# Pulse_Ox_PCB_board.net
KiCad netlist of a schematic drawn in EAGLE
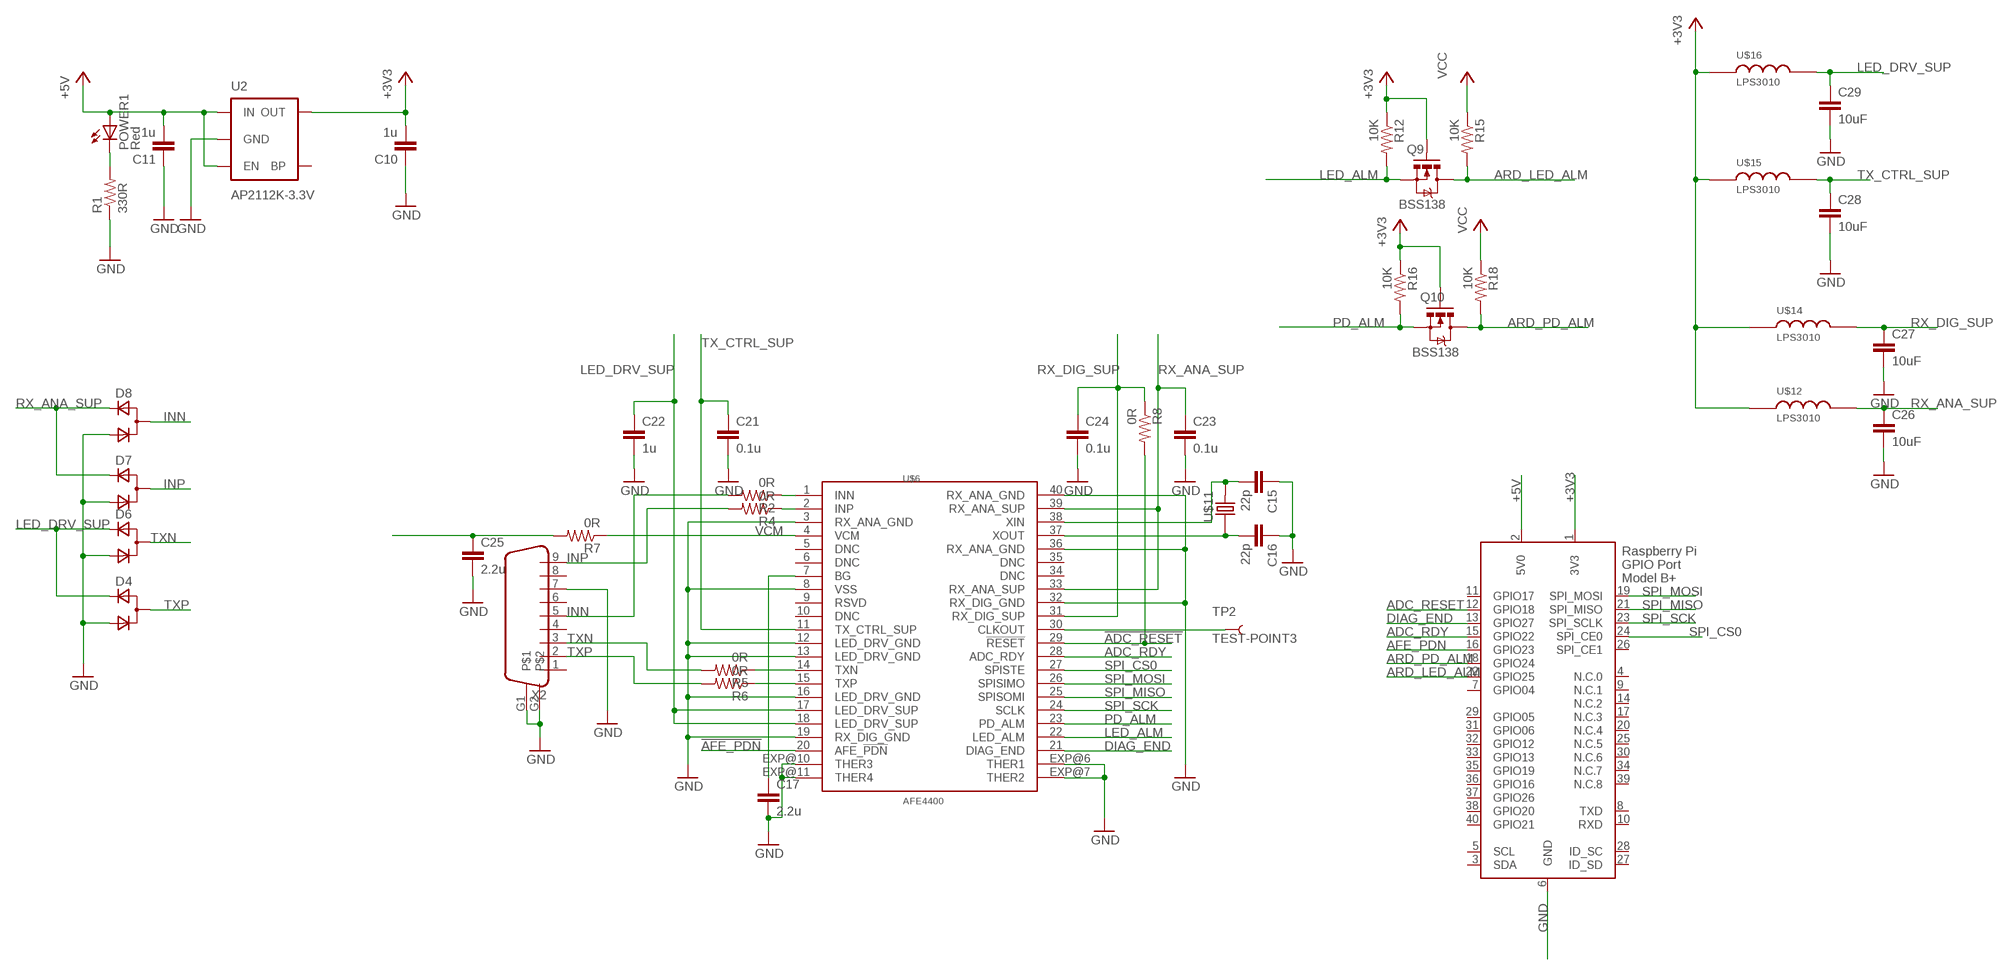
[diagram p0: schematic, sheet 1]

(export (version "E")
  (design (tool "Eeschema 10.0.6"))
  (components
    (comp (ref "C10")
      (value "1u")
      (footprint "eagle-import:C0805")
      (libsource (lib "eagle-import") (part "C-EUC0805"))
    )
    (comp (ref "C11")
      (value "1u")
      (footprint "eagle-import:C0805")
      (libsource (lib "eagle-import") (part "C-EUC0805"))
    )
    (comp (ref "C15")
      (value "22p")
      (footprint "eagle-import:C0402")
      (libsource (lib "eagle-import") (part "C-EUC0402"))
    )
    (comp (ref "C16")
      (value "22p")
      (footprint "eagle-import:C0402")
      (libsource (lib "eagle-import") (part "C-EUC0402"))
    )
    (comp (ref "C17")
      (value "2.2u")
      (footprint "eagle-import:C0402")
      (libsource (lib "eagle-import") (part "C-EUC0402"))
    )
    (comp (ref "C21")
      (value "0.1u")
      (footprint "eagle-import:C0805")
      (libsource (lib "eagle-import") (part "C-EUC0805"))
    )
    (comp (ref "C22")
      (value "1u")
      (footprint "eagle-import:C0805")
      (libsource (lib "eagle-import") (part "C-EUC0805"))
    )
    (comp (ref "C23")
      (value "0.1u")
      (footprint "eagle-import:C0805")
      (libsource (lib "eagle-import") (part "C-EUC0805"))
    )
    (comp (ref "C24")
      (value "0.1u")
      (footprint "eagle-import:C0805")
      (libsource (lib "eagle-import") (part "C-EUC0805"))
    )
    (comp (ref "C25")
      (value "2.2u")
      (footprint "eagle-import:C0402")
      (libsource (lib "eagle-import") (part "C-EUC0402"))
    )
    (comp (ref "C26")
      (value "10uF")
      (footprint "eagle-import:C0805")
      (libsource (lib "eagle-import") (part "C-EUC0805"))
    )
    (comp (ref "C27")
      (value "10uF")
      (footprint "eagle-import:C0805")
      (libsource (lib "eagle-import") (part "C-EUC0805"))
    )
    (comp (ref "C28")
      (value "10uF")
      (footprint "eagle-import:C0805")
      (libsource (lib "eagle-import") (part "C-EUC0805"))
    )
    (comp (ref "C29")
      (value "10uF")
      (footprint "eagle-import:C0805")
      (libsource (lib "eagle-import") (part "C-EUC0805"))
    )
    (comp (ref "D4")
      (value "D_ACACSOT323")
      (footprint "eagle-import:SOT323")
      (libsource (lib "eagle-import") (part "D_ACACSOT323"))
    )
    (comp (ref "D6")
      (value "D_ACACSOT323")
      (footprint "eagle-import:SOT323")
      (libsource (lib "eagle-import") (part "D_ACACSOT323"))
    )
    (comp (ref "D7")
      (value "D_ACACSOT323")
      (footprint "eagle-import:SOT323")
      (libsource (lib "eagle-import") (part "D_ACACSOT323"))
    )
    (comp (ref "D8")
      (value "D_ACACSOT323")
      (footprint "eagle-import:SOT323")
      (libsource (lib "eagle-import") (part "D_ACACSOT323"))
    )
    (comp (ref "POWER1")
      (value "Red")
      (footprint "eagle-import:CHIPLED_0603")
      (libsource (lib "eagle-import") (part "LEDCHIPLED_0603"))
    )
    (comp (ref "Q9")
      (value "BSS138")
      (footprint "eagle-import:SOT23-3")
      (libsource (lib "eagle-import") (part "MOSFET-NCHANNELSMD"))
    )
    (comp (ref "Q10")
      (value "BSS138")
      (footprint "eagle-import:SOT23-3")
      (libsource (lib "eagle-import") (part "MOSFET-NCHANNELSMD"))
    )
    (comp (ref "R1")
      (value "330R")
      (footprint "eagle-import:R0805")
      (libsource (lib "eagle-import") (part "R-US_R0805"))
    )
    (comp (ref "R2")
      (value "0R")
      (footprint "eagle-import:R0402")
      (libsource (lib "eagle-import") (part "R-US_R0402"))
    )
    (comp (ref "R4")
      (value "0R")
      (footprint "eagle-import:R0402")
      (libsource (lib "eagle-import") (part "R-US_R0402"))
    )
    (comp (ref "R5")
      (value "0R")
      (footprint "eagle-import:R0805")
      (libsource (lib "eagle-import") (part "R-US_R0805"))
    )
    (comp (ref "R6")
      (value "0R")
      (footprint "eagle-import:R0805")
      (libsource (lib "eagle-import") (part "R-US_R0805"))
    )
    (comp (ref "R7")
      (value "0R")
      (footprint "eagle-import:R0402")
      (libsource (lib "eagle-import") (part "R-US_R0402"))
    )
    (comp (ref "R8")
      (value "0R")
      (footprint "eagle-import:R0805")
      (libsource (lib "eagle-import") (part "R-US_R0805"))
    )
    (comp (ref "R12")
      (value "10K")
      (footprint "eagle-import:0805")
      (libsource (lib "eagle-import") (part "RESISTOR0805-RES"))
    )
    (comp (ref "R15")
      (value "10K")
      (footprint "eagle-import:0805")
      (libsource (lib "eagle-import") (part "RESISTOR0805-RES"))
    )
    (comp (ref "R16")
      (value "10K")
      (footprint "eagle-import:0805")
      (libsource (lib "eagle-import") (part "RESISTOR0805-RES"))
    )
    (comp (ref "R18")
      (value "10K")
      (footprint "eagle-import:0805")
      (libsource (lib "eagle-import") (part "RESISTOR0805-RES"))
    )
    (comp (ref "TP2")
      (value "TEST-POINT3")
      (footprint "eagle-import:PAD.03X.03")
      (libsource (lib "eagle-import") (part "TEST-POINT3"))
    )
    (comp (ref "U$6")
      (value "AFE4400")
      (footprint "eagle-import:QFN-40")
      (libsource (lib "eagle-import") (part "AFE4400"))
    )
    (comp (ref "U$11")
      (value "ABM3")
      (footprint "eagle-import:ABM3")
      (libsource (lib "eagle-import") (part "ABM3"))
    )
    (comp (ref "U$12")
      (value "LPS3010")
      (footprint "eagle-import:LPS")
      (libsource (lib "eagle-import") (part "LPS"))
    )
    (comp (ref "U$14")
      (value "LPS3010")
      (footprint "eagle-import:LPS")
      (libsource (lib "eagle-import") (part "LPS"))
    )
    (comp (ref "U$15")
      (value "LPS3010")
      (footprint "eagle-import:LPS")
      (libsource (lib "eagle-import") (part "LPS"))
    )
    (comp (ref "U$16")
      (value "LPS3010")
      (footprint "eagle-import:LPS")
      (libsource (lib "eagle-import") (part "LPS"))
    )
    (comp (ref "U2")
      (value "AP2112K-3.3V")
      (footprint "eagle-import:SOT23-5")
      (libsource (lib "eagle-import") (part "V_REG_LDOSMD"))
    )
    (comp (ref "X2")
      (value "DB9")
      (footprint "eagle-import:DB9")
      (libsource (lib "eagle-import") (part "DB9"))
    )
    (comp (ref "X3")
      (value "RASPI_BOARD_B+_HD")
      (footprint "eagle-import:RASPI_BOARD_B+HAT_DF")
      (libsource (lib "eagle-import") (part "RASPI_BOARD_B+_HD"))
    )
  )
  (nets
    (net (code "1") (name "+3V3") (class "Default")
      (node (ref "C10") (pin "2") (pinfunction "2_2") (pintype "passive"))
      (node (ref "Q10") (pin "1") (pinfunction "G_1") (pintype "passive"))
      (node (ref "Q9") (pin "1") (pinfunction "G_1") (pintype "passive"))
      (node (ref "R12") (pin "1") (pinfunction "1_1") (pintype "passive"))
      (node (ref "R16") (pin "1") (pinfunction "1_1") (pintype "passive"))
      (node (ref "U$12") (pin "1") (pinfunction "P$1_1") (pintype "bidirectional"))
      (node (ref "U$14") (pin "1") (pinfunction "P$1_1") (pintype "bidirectional"))
      (node (ref "U$15") (pin "1") (pinfunction "P$1_1") (pintype "bidirectional"))
      (node (ref "U$16") (pin "1") (pinfunction "P$1_1") (pintype "bidirectional"))
      (node (ref "U2") (pin "5") (pinfunction "OUT_5") (pintype "passive"))
      (node (ref "X3") (pin "1") (pinfunction "3V3_1") (pintype "power_in"))
    )
    (net (code "2") (name "+5V") (class "Default")
      (node (ref "C11") (pin "2") (pinfunction "2_2") (pintype "passive"))
      (node (ref "POWER1") (pin "A") (pinfunction "A_A") (pintype "passive"))
      (node (ref "U2") (pin "1") (pinfunction "IN_1") (pintype "input"))
      (node (ref "U2") (pin "3") (pinfunction "EN_3") (pintype "input"))
      (node (ref "X3") (pin "2") (pinfunction "5V0_2") (pintype "power_in"))
    )
    (net (code "3") (name "/ADC_RDY") (class "Default")
      (node (ref "U$6") (pin "28") (pinfunction "ADC_RDY_28") (pintype "bidirectional"))
      (node (ref "X3") (pin "15") (pinfunction "GPIO22_15") (pintype "bidirectional"))
    )
    (net (code "4") (name "/ADC_RESET") (class "Default")
      (node (ref "X3") (pin "12") (pinfunction "GPIO18_12") (pintype "bidirectional"))
    )
    (net (code "5") (name "/AFE_PDN") (class "Default")
      (node (ref "X3") (pin "16") (pinfunction "GPIO23_16") (pintype "bidirectional"))
    )
    (net (code "6") (name "/ARD_LED_ALM") (class "Default")
      (node (ref "Q9") (pin "3") (pinfunction "D_3") (pintype "passive"))
      (node (ref "R15") (pin "2") (pinfunction "2_2") (pintype "passive"))
      (node (ref "X3") (pin "22") (pinfunction "GPIO25_22") (pintype "bidirectional"))
    )
    (net (code "7") (name "/ARD_PD_ALM") (class "Default")
      (node (ref "Q10") (pin "3") (pinfunction "D_3") (pintype "passive"))
      (node (ref "R18") (pin "2") (pinfunction "2_2") (pintype "passive"))
      (node (ref "X3") (pin "18") (pinfunction "GPIO24_18") (pintype "bidirectional"))
    )
    (net (code "8") (name "/DIAG_END") (class "Default")
      (node (ref "U$6") (pin "21") (pinfunction "DIAG_END_21") (pintype "bidirectional"))
      (node (ref "X3") (pin "13") (pinfunction "GPIO27_13") (pintype "bidirectional"))
    )
    (net (code "9") (name "/INN") (class "Default")
      (node (ref "D8") (pin "1") (pinfunction "CA_1") (pintype "passive"))
      (node (ref "R2") (pin "2") (pinfunction "2_2") (pintype "passive"))
      (node (ref "X2") (pin "5") (pinfunction "5_5") (pintype "passive"))
    )
    (net (code "10") (name "/INP") (class "Default")
      (node (ref "D7") (pin "1") (pinfunction "CA_1") (pintype "passive"))
      (node (ref "R4") (pin "2") (pinfunction "2_2") (pintype "passive"))
      (node (ref "X2") (pin "9") (pinfunction "9_9") (pintype "passive"))
    )
    (net (code "11") (name "/LED_ALM") (class "Default")
      (node (ref "Q9") (pin "2") (pinfunction "S_2") (pintype "passive"))
      (node (ref "R12") (pin "2") (pinfunction "2_2") (pintype "passive"))
      (node (ref "U$6") (pin "22") (pinfunction "LED_ALM_22") (pintype "bidirectional"))
    )
    (net (code "12") (name "/LED_DRV_SUP") (class "Default")
      (node (ref "C22") (pin "1") (pinfunction "1_1") (pintype "passive"))
      (node (ref "C29") (pin "1") (pinfunction "1_1") (pintype "passive"))
      (node (ref "D4") (pin "3") (pinfunction "A_3") (pintype "passive"))
      (node (ref "D6") (pin "3") (pinfunction "A_3") (pintype "passive"))
      (node (ref "U$16") (pin "2") (pinfunction "P$2_2") (pintype "bidirectional"))
      (node (ref "U$6") (pin "17") (pinfunction "LED_DRV_SUP_17") (pintype "bidirectional"))
      (node (ref "U$6") (pin "18") (pinfunction "LED_DRV_SUP_18") (pintype "bidirectional"))
    )
    (net (code "13") (name "/PD_ALM") (class "Default")
      (node (ref "Q10") (pin "2") (pinfunction "S_2") (pintype "passive"))
      (node (ref "R16") (pin "2") (pinfunction "2_2") (pintype "passive"))
      (node (ref "U$6") (pin "23") (pinfunction "PD_ALM_23") (pintype "bidirectional"))
    )
    (net (code "14") (name "/RX_ANA_SUP") (class "Default")
      (node (ref "C23") (pin "1") (pinfunction "1_1") (pintype "passive"))
      (node (ref "C26") (pin "1") (pinfunction "1_1") (pintype "passive"))
      (node (ref "D7") (pin "3") (pinfunction "A_3") (pintype "passive"))
      (node (ref "D8") (pin "3") (pinfunction "A_3") (pintype "passive"))
      (node (ref "U$12") (pin "2") (pinfunction "P$2_2") (pintype "bidirectional"))
      (node (ref "U$6") (pin "33") (pinfunction "RX_ANA_SUP_33") (pintype "bidirectional"))
      (node (ref "U$6") (pin "39") (pinfunction "RX_ANA_SUP_39") (pintype "bidirectional"))
    )
    (net (code "15") (name "/RX_DIG_SUP") (class "Default")
      (node (ref "C24") (pin "1") (pinfunction "1_1") (pintype "passive"))
      (node (ref "C27") (pin "1") (pinfunction "1_1") (pintype "passive"))
      (node (ref "R8") (pin "1") (pinfunction "1_1") (pintype "passive"))
      (node (ref "U$14") (pin "2") (pinfunction "P$2_2") (pintype "bidirectional"))
      (node (ref "U$6") (pin "31") (pinfunction "RX_DIG_SUP_31") (pintype "bidirectional"))
    )
    (net (code "16") (name "/SPI_CS0") (class "Default")
      (node (ref "U$6") (pin "27") (pinfunction "SPISTE_27") (pintype "bidirectional"))
      (node (ref "X3") (pin "24") (pinfunction "SPI_CE0_24") (pintype "bidirectional"))
    )
    (net (code "17") (name "/SPI_MISO") (class "Default")
      (node (ref "U$6") (pin "25") (pinfunction "SPISOMI_25") (pintype "bidirectional"))
      (node (ref "X3") (pin "21") (pinfunction "SPI_MISO_21") (pintype "bidirectional"))
    )
    (net (code "18") (name "/SPI_MOSI") (class "Default")
      (node (ref "U$6") (pin "26") (pinfunction "SPISIMO_26") (pintype "bidirectional"))
      (node (ref "X3") (pin "19") (pinfunction "SPI_MOSI_19") (pintype "bidirectional"))
    )
    (net (code "19") (name "/SPI_SCK") (class "Default")
      (node (ref "U$6") (pin "24") (pinfunction "SCLK_24") (pintype "bidirectional"))
      (node (ref "X3") (pin "23") (pinfunction "SPI_SCLK_23") (pintype "bidirectional"))
    )
    (net (code "20") (name "/TXN") (class "Default")
      (node (ref "D6") (pin "1") (pinfunction "CA_1") (pintype "passive"))
      (node (ref "R5") (pin "2") (pinfunction "2_2") (pintype "passive"))
      (node (ref "X2") (pin "3") (pinfunction "3_3") (pintype "passive"))
    )
    (net (code "21") (name "/TXP") (class "Default")
      (node (ref "D4") (pin "1") (pinfunction "CA_1") (pintype "passive"))
      (node (ref "R6") (pin "2") (pinfunction "2_2") (pintype "passive"))
      (node (ref "X2") (pin "2") (pinfunction "2_2") (pintype "passive"))
    )
    (net (code "22") (name "/TX_CTRL_SUP") (class "Default")
      (node (ref "C21") (pin "1") (pinfunction "1_1") (pintype "passive"))
      (node (ref "C28") (pin "1") (pinfunction "1_1") (pintype "passive"))
      (node (ref "U$15") (pin "2") (pinfunction "P$2_2") (pintype "bidirectional"))
      (node (ref "U$6") (pin "11") (pinfunction "TX_CTRL_SUP_11") (pintype "bidirectional"))
    )
    (net (code "23") (name "/VCM") (class "Default")
      (node (ref "R7") (pin "1") (pinfunction "1_1") (pintype "passive"))
      (node (ref "U$6") (pin "4") (pinfunction "VCM_4") (pintype "bidirectional"))
    )
    (net (code "24") (name "/~{ADC_RESET}") (class "Default")
      (node (ref "R8") (pin "2") (pinfunction "2_2") (pintype "passive"))
      (node (ref "U$6") (pin "29") (pinfunction "~{RESET}_29") (pintype "bidirectional"))
    )
    (net (code "25") (name "/~{AFE_PDN}") (class "Default")
      (node (ref "U$6") (pin "20") (pinfunction "AFE_~{PDN}_20") (pintype "bidirectional"))
    )
    (net (code "26") (name "GND") (class "Default")
      (node (ref "C10") (pin "1") (pinfunction "1_1") (pintype "passive"))
      (node (ref "C11") (pin "1") (pinfunction "1_1") (pintype "passive"))
      (node (ref "C15") (pin "1") (pinfunction "1_1") (pintype "passive"))
      (node (ref "C16") (pin "1") (pinfunction "1_1") (pintype "passive"))
      (node (ref "C17") (pin "2") (pinfunction "2_2") (pintype "passive"))
      (node (ref "C21") (pin "2") (pinfunction "2_2") (pintype "passive"))
      (node (ref "C22") (pin "2") (pinfunction "2_2") (pintype "passive"))
      (node (ref "C23") (pin "2") (pinfunction "2_2") (pintype "passive"))
      (node (ref "C24") (pin "2") (pinfunction "2_2") (pintype "passive"))
      (node (ref "C25") (pin "2") (pinfunction "2_2") (pintype "passive"))
      (node (ref "C26") (pin "2") (pinfunction "2_2") (pintype "passive"))
      (node (ref "C27") (pin "2") (pinfunction "2_2") (pintype "passive"))
      (node (ref "C28") (pin "2") (pinfunction "2_2") (pintype "passive"))
      (node (ref "C29") (pin "2") (pinfunction "2_2") (pintype "passive"))
      (node (ref "D4") (pin "2") (pinfunction "C_2") (pintype "passive"))
      (node (ref "D6") (pin "2") (pinfunction "C_2") (pintype "passive"))
      (node (ref "D7") (pin "2") (pinfunction "C_2") (pintype "passive"))
      (node (ref "D8") (pin "2") (pinfunction "C_2") (pintype "passive"))
      (node (ref "R1") (pin "1") (pinfunction "1_1") (pintype "passive"))
      (node (ref "U$6") (pin "12") (pinfunction "LED_DRV_GND_12") (pintype "bidirectional"))
      (node (ref "U$6") (pin "13") (pinfunction "LED_DRV_GND_13") (pintype "bidirectional"))
      (node (ref "U$6") (pin "16") (pinfunction "LED_DRV_GND_16") (pintype "bidirectional"))
      (node (ref "U$6") (pin "19") (pinfunction "RX_DIG_GND_19") (pintype "bidirectional"))
      (node (ref "U$6") (pin "3") (pinfunction "RX_ANA_GND_3") (pintype "bidirectional"))
      (node (ref "U$6") (pin "32") (pinfunction "RX_DIG_GND_32") (pintype "bidirectional"))
      (node (ref "U$6") (pin "36") (pinfunction "RX_ANA_GND_36") (pintype "bidirectional"))
      (node (ref "U$6") (pin "40") (pinfunction "RX_ANA_GND_40") (pintype "bidirectional"))
      (node (ref "U$6") (pin "8") (pinfunction "VSS_8") (pintype "bidirectional"))
      (node (ref "U$6") (pin "EXP@10") (pinfunction "THER3_EXP@10") (pintype "bidirectional"))
      (node (ref "U$6") (pin "EXP@11") (pinfunction "THER4_EXP@11") (pintype "bidirectional"))
      (node (ref "U$6") (pin "EXP@6") (pinfunction "THER1_EXP@6") (pintype "bidirectional"))
      (node (ref "U$6") (pin "EXP@7") (pinfunction "THER2_EXP@7") (pintype "bidirectional"))
      (node (ref "U2") (pin "2") (pinfunction "GND_2") (pintype "input"))
      (node (ref "X2") (pin "7") (pinfunction "7_7") (pintype "passive"))
      (node (ref "X2") (pin "G1") (pinfunction "P$1_G1") (pintype "bidirectional"))
      (node (ref "X2") (pin "G2") (pinfunction "P$2_G2") (pintype "bidirectional"))
      (node (ref "X3") (pin "6") (pinfunction "GND_6") (pintype "power_in"))
    )
    (net (code "27") (name "Net-(C25-Pad1)") (class "Default")
      (node (ref "C25") (pin "1") (pinfunction "1_1") (pintype "passive"))
      (node (ref "R7") (pin "2") (pinfunction "2_2") (pintype "passive"))
    )
    (net (code "28") (name "Net-(POWER1-PadC)") (class "Default")
      (node (ref "POWER1") (pin "C") (pinfunction "C_C") (pintype "passive"))
      (node (ref "R1") (pin "2") (pinfunction "2_2") (pintype "passive"))
    )
    (net (code "29") (name "Net-(TP2-1)") (class "Default")
      (node (ref "TP2") (pin "P$1") (pinfunction "1_P$1") (pintype "bidirectional"))
      (node (ref "U$6") (pin "30") (pinfunction "CLKOUT_30") (pintype "bidirectional"))
    )
    (net (code "30") (name "Net-(U$6-BG)") (class "Default")
      (node (ref "C17") (pin "1") (pinfunction "1_1") (pintype "passive"))
      (node (ref "U$6") (pin "7") (pinfunction "BG_7") (pintype "bidirectional"))
    )
    (net (code "31") (name "Net-(U$6-INN)") (class "Default")
      (node (ref "R2") (pin "1") (pinfunction "1_1") (pintype "passive"))
      (node (ref "U$6") (pin "1") (pinfunction "INN_1") (pintype "bidirectional"))
    )
    (net (code "32") (name "Net-(U$6-INP)") (class "Default")
      (node (ref "R4") (pin "1") (pinfunction "1_1") (pintype "passive"))
      (node (ref "U$6") (pin "2") (pinfunction "INP_2") (pintype "bidirectional"))
    )
    (net (code "33") (name "Net-(U$6-TXN)") (class "Default")
      (node (ref "R5") (pin "1") (pinfunction "1_1") (pintype "passive"))
      (node (ref "U$6") (pin "14") (pinfunction "TXN_14") (pintype "bidirectional"))
    )
    (net (code "34") (name "Net-(U$6-TXP)") (class "Default")
      (node (ref "R6") (pin "1") (pinfunction "1_1") (pintype "passive"))
      (node (ref "U$6") (pin "15") (pinfunction "TXP_15") (pintype "bidirectional"))
    )
    (net (code "35") (name "Net-(U$6-XIN)") (class "Default")
      (node (ref "C15") (pin "2") (pinfunction "2_2") (pintype "passive"))
      (node (ref "U$11") (pin "2") (pinfunction "2_2") (pintype "passive"))
      (node (ref "U$6") (pin "38") (pinfunction "XIN_38") (pintype "bidirectional"))
    )
    (net (code "36") (name "Net-(U$6-XOUT)") (class "Default")
      (node (ref "C16") (pin "2") (pinfunction "2_2") (pintype "passive"))
      (node (ref "U$11") (pin "1") (pinfunction "1_1") (pintype "passive"))
      (node (ref "U$6") (pin "37") (pinfunction "XOUT_37") (pintype "bidirectional"))
    )
    (net (code "37") (name "VCC") (class "Default")
      (node (ref "R15") (pin "1") (pinfunction "1_1") (pintype "passive"))
      (node (ref "R18") (pin "1") (pinfunction "1_1") (pintype "passive"))
    )
    (net (code "38") (name "unconnected-(U$6-DNC-Pad5)") (class "Default")
      (node (ref "U$6") (pin "5") (pinfunction "DNC_5") (pintype "bidirectional"))
    )
    (net (code "39") (name "unconnected-(U$6-DNC-Pad6)") (class "Default")
      (node (ref "U$6") (pin "6") (pinfunction "DNC_6") (pintype "bidirectional"))
    )
    (net (code "40") (name "unconnected-(U$6-DNC-Pad10)") (class "Default")
      (node (ref "U$6") (pin "10") (pinfunction "DNC_10") (pintype "bidirectional"))
    )
    (net (code "41") (name "unconnected-(U$6-DNC-Pad34)") (class "Default")
      (node (ref "U$6") (pin "34") (pinfunction "DNC_34") (pintype "bidirectional"))
    )
    (net (code "42") (name "unconnected-(U$6-DNC-Pad35)") (class "Default")
      (node (ref "U$6") (pin "35") (pinfunction "DNC_35") (pintype "bidirectional"))
    )
    (net (code "43") (name "unconnected-(U$6-RSVD-Pad9)") (class "Default")
      (node (ref "U$6") (pin "9") (pinfunction "RSVD_9") (pintype "bidirectional"))
    )
    (net (code "44") (name "unconnected-(U2-BP-Pad4)") (class "Default")
      (node (ref "U2") (pin "4") (pinfunction "BP_4") (pintype "input"))
    )
    (net (code "45") (name "unconnected-(X2-Pad1)") (class "Default")
      (node (ref "X2") (pin "1") (pinfunction "1_1") (pintype "passive"))
    )
    (net (code "46") (name "unconnected-(X2-Pad4)") (class "Default")
      (node (ref "X2") (pin "4") (pinfunction "4_4") (pintype "passive"))
    )
    (net (code "47") (name "unconnected-(X2-Pad6)") (class "Default")
      (node (ref "X2") (pin "6") (pinfunction "6_6") (pintype "passive"))
    )
    (net (code "48") (name "unconnected-(X2-Pad8)") (class "Default")
      (node (ref "X2") (pin "8") (pinfunction "8_8") (pintype "passive"))
    )
    (net (code "49") (name "unconnected-(X3-GPIO04-Pad7)") (class "Default")
      (node (ref "X3") (pin "7") (pinfunction "GPIO04_7") (pintype "bidirectional"))
    )
    (net (code "50") (name "unconnected-(X3-GPIO05-Pad29)") (class "Default")
      (node (ref "X3") (pin "29") (pinfunction "GPIO05_29") (pintype "no_connect"))
    )
    (net (code "51") (name "unconnected-(X3-GPIO06-Pad31)") (class "Default")
      (node (ref "X3") (pin "31") (pinfunction "GPIO06_31") (pintype "no_connect"))
    )
    (net (code "52") (name "unconnected-(X3-GPIO12-Pad32)") (class "Default")
      (node (ref "X3") (pin "32") (pinfunction "GPIO12_32") (pintype "no_connect"))
    )
    (net (code "53") (name "unconnected-(X3-GPIO13-Pad33)") (class "Default")
      (node (ref "X3") (pin "33") (pinfunction "GPIO13_33") (pintype "no_connect"))
    )
    (net (code "54") (name "unconnected-(X3-GPIO16-Pad36)") (class "Default")
      (node (ref "X3") (pin "36") (pinfunction "GPIO16_36") (pintype "no_connect"))
    )
    (net (code "55") (name "unconnected-(X3-GPIO17-Pad11)") (class "Default")
      (node (ref "X3") (pin "11") (pinfunction "GPIO17_11") (pintype "bidirectional"))
    )
    (net (code "56") (name "unconnected-(X3-GPIO19-Pad35)") (class "Default")
      (node (ref "X3") (pin "35") (pinfunction "GPIO19_35") (pintype "no_connect"))
    )
    (net (code "57") (name "unconnected-(X3-GPIO20-Pad38)") (class "Default")
      (node (ref "X3") (pin "38") (pinfunction "GPIO20_38") (pintype "no_connect"))
    )
    (net (code "58") (name "unconnected-(X3-GPIO21-Pad40)") (class "Default")
      (node (ref "X3") (pin "40") (pinfunction "GPIO21_40") (pintype "no_connect"))
    )
    (net (code "59") (name "unconnected-(X3-GPIO26-Pad37)") (class "Default")
      (node (ref "X3") (pin "37") (pinfunction "GPIO26_37") (pintype "no_connect"))
    )
    (net (code "60") (name "unconnected-(X3-ID_SC-Pad28)") (class "Default")
      (node (ref "X3") (pin "28") (pinfunction "ID_SC_28") (pintype "no_connect"))
    )
    (net (code "61") (name "unconnected-(X3-ID_SD-Pad27)") (class "Default")
      (node (ref "X3") (pin "27") (pinfunction "ID_SD_27") (pintype "no_connect"))
    )
    (net (code "62") (name "unconnected-(X3-N.C.0-Pad4)") (class "Default")
      (node (ref "X3") (pin "4") (pinfunction "N.C.0_4") (pintype "no_connect"))
    )
    (net (code "63") (name "unconnected-(X3-N.C.1-Pad9)") (class "Default")
      (node (ref "X3") (pin "9") (pinfunction "N.C.1_9") (pintype "no_connect"))
    )
    (net (code "64") (name "unconnected-(X3-N.C.2-Pad14)") (class "Default")
      (node (ref "X3") (pin "14") (pinfunction "N.C.2_14") (pintype "no_connect"))
    )
    (net (code "65") (name "unconnected-(X3-N.C.3-Pad17)") (class "Default")
      (node (ref "X3") (pin "17") (pinfunction "N.C.3_17") (pintype "no_connect"))
    )
    (net (code "66") (name "unconnected-(X3-N.C.4-Pad20)") (class "Default")
      (node (ref "X3") (pin "20") (pinfunction "N.C.4_20") (pintype "no_connect"))
    )
    (net (code "67") (name "unconnected-(X3-N.C.5-Pad25)") (class "Default")
      (node (ref "X3") (pin "25") (pinfunction "N.C.5_25") (pintype "no_connect"))
    )
    (net (code "68") (name "unconnected-(X3-N.C.6-Pad30)") (class "Default")
      (node (ref "X3") (pin "30") (pinfunction "N.C.6_30") (pintype "no_connect"))
    )
    (net (code "69") (name "unconnected-(X3-N.C.7-Pad34)") (class "Default")
      (node (ref "X3") (pin "34") (pinfunction "N.C.7_34") (pintype "no_connect"))
    )
    (net (code "70") (name "unconnected-(X3-N.C.8-Pad39)") (class "Default")
      (node (ref "X3") (pin "39") (pinfunction "N.C.8_39") (pintype "no_connect"))
    )
    (net (code "71") (name "unconnected-(X3-RXD-Pad10)") (class "Default")
      (node (ref "X3") (pin "10") (pinfunction "RXD_10") (pintype "bidirectional"))
    )
    (net (code "72") (name "unconnected-(X3-SCL-Pad5)") (class "Default")
      (node (ref "X3") (pin "5") (pinfunction "SCL_5") (pintype "bidirectional"))
    )
    (net (code "73") (name "unconnected-(X3-SDA-Pad3)") (class "Default")
      (node (ref "X3") (pin "3") (pinfunction "SDA_3") (pintype "bidirectional"))
    )
    (net (code "74") (name "unconnected-(X3-SPI_CE1-Pad26)") (class "Default")
      (node (ref "X3") (pin "26") (pinfunction "SPI_CE1_26") (pintype "bidirectional"))
    )
    (net (code "75") (name "unconnected-(X3-TXD-Pad8)") (class "Default")
      (node (ref "X3") (pin "8") (pinfunction "TXD_8") (pintype "bidirectional"))
    )
  )
)
